# ProjectSchematic.net
KiCad netlist of a schematic drawn in EAGLE
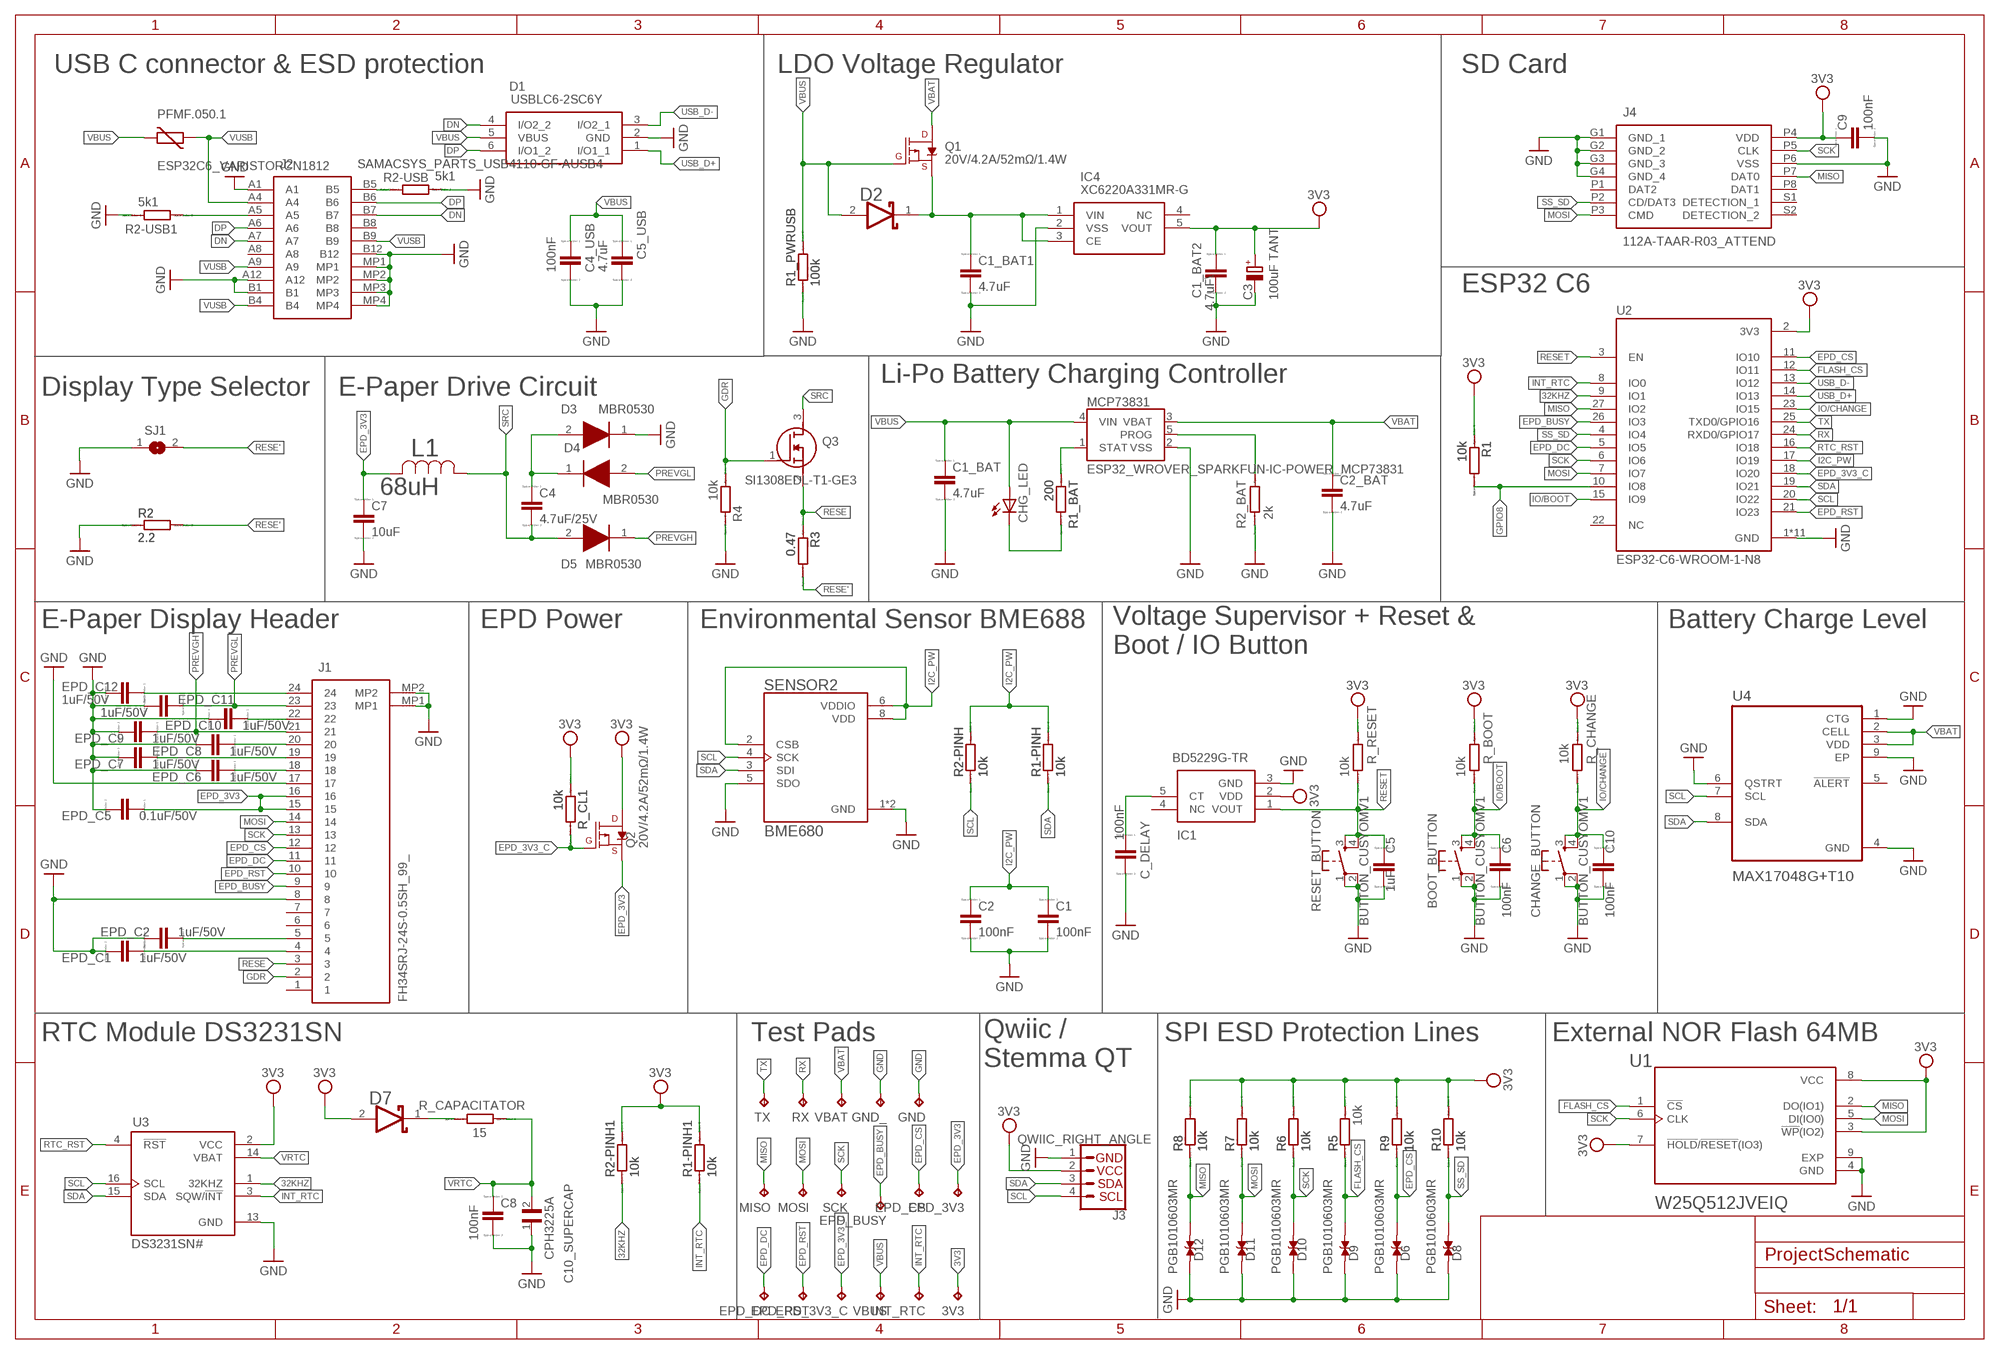
[diagram p0: schematic, sheet 1]

(export (version "E")
  (design (tool "Eeschema 10.0.6"))
  (components
    (comp (ref "3V3")
      (value "TPTP20R")
      (footprint "eagle-import:TP20R")
      (libsource (lib "eagle-import") (part "TPTP20R"))
    )
    (comp (ref "BOOT_BUTTON")
      (value "BUTTON_CUSYOMV1")
      (footprint "eagle-import:MYBUTTON")
      (libsource (lib "eagle-import") (part "BUTTON_CUSYOMV1"))
    )
    (comp (ref "C1")
      (value "100nF")
      (footprint "eagle-import:ESP32_WROVER_EAGLE-LTSPICE_C0402")
      (libsource (lib "eagle-import") (part "ESP32_WROVER_EAGLE-LTSPICE_CC0402"))
    )
    (comp (ref "C1_BAT")
      (value "4.7uF")
      (footprint "eagle-import:ESP32_WROVER_EAGLE-LTSPICE_C0402")
      (libsource (lib "eagle-import") (part "ESP32_WROVER_EAGLE-LTSPICE_CC0402"))
    )
    (comp (ref "C1_BAT1")
      (value "4.7uF")
      (footprint "eagle-import:ESP32_WROVER_EAGLE-LTSPICE_C0402")
      (libsource (lib "eagle-import") (part "ESP32_WROVER_EAGLE-LTSPICE_CC0402"))
    )
    (comp (ref "C1_BAT2")
      (value "4.7uF\\")
      (footprint "eagle-import:ESP32_WROVER_EAGLE-LTSPICE_C0402")
      (libsource (lib "eagle-import") (part "ESP32_WROVER_EAGLE-LTSPICE_CC0402"))
    )
    (comp (ref "C2")
      (value "100nF")
      (footprint "eagle-import:ESP32_WROVER_EAGLE-LTSPICE_C0402")
      (libsource (lib "eagle-import") (part "ESP32_WROVER_EAGLE-LTSPICE_CC0402"))
    )
    (comp (ref "C2_BAT")
      (value "4.7uF")
      (footprint "eagle-import:ESP32_WROVER_EAGLE-LTSPICE_C0402")
      (libsource (lib "eagle-import") (part "ESP32_WROVER_EAGLE-LTSPICE_CC0402"))
    )
    (comp (ref "C3")
      (value "100uF TANT")
      (footprint "eagle-import:RCL_CT3528")
      (libsource (lib "eagle-import") (part "RCL_CPOL-EUCT3528"))
    )
    (comp (ref "C4")
      (value "4.7uF/25V")
      (footprint "eagle-import:ESP32_WROVER_EAGLE-LTSPICE_C0402")
      (libsource (lib "eagle-import") (part "ESP32_WROVER_EAGLE-LTSPICE_CC0402"))
    )
    (comp (ref "C4_USB")
      (value "100nF")
      (footprint "eagle-import:ESP32_WROVER_EAGLE-LTSPICE_C0402")
      (libsource (lib "eagle-import") (part "ESP32_WROVER_EAGLE-LTSPICE_CC0402"))
    )
    (comp (ref "C5")
      (value "1uF")
      (footprint "eagle-import:ESP32_WROVER_EAGLE-LTSPICE_C0402")
      (libsource (lib "eagle-import") (part "ESP32_WROVER_EAGLE-LTSPICE_CC0402"))
    )
    (comp (ref "C5_USB")
      (value "4.7uF")
      (footprint "eagle-import:ESP32_WROVER_EAGLE-LTSPICE_C0402")
      (libsource (lib "eagle-import") (part "ESP32_WROVER_EAGLE-LTSPICE_CC0402"))
    )
    (comp (ref "C6")
      (value "100nF")
      (footprint "eagle-import:ESP32_WROVER_EAGLE-LTSPICE_C0402")
      (libsource (lib "eagle-import") (part "ESP32_WROVER_EAGLE-LTSPICE_CC0402"))
    )
    (comp (ref "C7")
      (value "10uF")
      (footprint "eagle-import:ESP32_WROVER_EAGLE-LTSPICE_C0402")
      (libsource (lib "eagle-import") (part "ESP32_WROVER_EAGLE-LTSPICE_CC0402"))
    )
    (comp (ref "C8")
      (value "100nF")
      (footprint "eagle-import:ESP32_WROVER_EAGLE-LTSPICE_C0402")
      (libsource (lib "eagle-import") (part "ESP32_WROVER_EAGLE-LTSPICE_CC0402"))
    )
    (comp (ref "C9")
      (value "100nF")
      (footprint "eagle-import:ESP32_WROVER_EAGLE-LTSPICE_C0402")
      (libsource (lib "eagle-import") (part "ESP32_WROVER_EAGLE-LTSPICE_CC0402"))
    )
    (comp (ref "C10")
      (value "100nF")
      (footprint "eagle-import:ESP32_WROVER_EAGLE-LTSPICE_C0402")
      (libsource (lib "eagle-import") (part "ESP32_WROVER_EAGLE-LTSPICE_CC0402"))
    )
    (comp (ref "C10_SUPERCAP")
      (value "CPH3225A")
      (footprint "eagle-import:CAPCP3225X100N")
      (fields (field (name "MF") "Seiko Instruments"))
      (libsource (lib "eagle-import") (part "CPH3225A"))
    )
    (comp (ref "CHANGE_BUTTON")
      (value "BUTTON_CUSYOMV1")
      (footprint "eagle-import:MYBUTTON")
      (libsource (lib "eagle-import") (part "BUTTON_CUSYOMV1"))
    )
    (comp (ref "CHG_LED")
      (value "ADAFRUIT_LEDCHIP-LED0603")
      (footprint "eagle-import:ADAFRUIT_CHIP-LED0603")
      (libsource (lib "eagle-import") (part "ADAFRUIT_LEDCHIP-LED0603"))
    )
    (comp (ref "C_DELAY")
      (value "100nF")
      (footprint "eagle-import:ESP32_WROVER_EAGLE-LTSPICE_C0402")
      (libsource (lib "eagle-import") (part "ESP32_WROVER_EAGLE-LTSPICE_CC0402"))
    )
    (comp (ref "D1")
      (value "USBLC6-2SC6Y")
      (footprint "eagle-import:SOT95P280X145-6N")
      (fields (field (name "MF") "STMicroelectronics"))
      (libsource (lib "eagle-import") (part "USBLC6-2SC6Y"))
    )
    (comp (ref "D2")
      (value "ESP32_WROVER_AVX---SD0805S020S1R0_AVX_SD0805S020S1R0_0_0AVX_SD0805S020S1R0_0_0")
      (footprint "eagle-import:ESP32_WROVER_AVX---SD0805S020S1R0_AVX_SD0805S020S1R0_0")
      (fields
        (field (name "DIGIKEY_PART_NUMBER") "478-7800-1-ND")
        (field (name "MF") "AVX")
        (field (name "MOUSER_PART_NUMBER") "581-SD0805S020S1R0")
      )
      (libsource (lib "eagle-import") (part "ESP32_WROVER_AVX---SD0805S020S1R0_AVX_SD0805S020S1R0_0_0AVX_SD0805S020S1R0_0_0"))
    )
    (comp (ref "D3")
      (value "MBR0530")
      (footprint "eagle-import:SOD3716X135N")
      (fields (field (name "MF") "ON Semiconductor"))
      (libsource (lib "eagle-import") (part "MBR0530"))
    )
    (comp (ref "D4")
      (value "MBR0530")
      (footprint "eagle-import:SOD3716X135N")
      (fields (field (name "MF") "ON Semiconductor"))
      (libsource (lib "eagle-import") (part "MBR0530"))
    )
    (comp (ref "D5")
      (value "MBR0530")
      (footprint "eagle-import:SOD3716X135N")
      (fields (field (name "MF") "ON Semiconductor"))
      (libsource (lib "eagle-import") (part "MBR0530"))
    )
    (comp (ref "D6")
      (value "PGB1010603MR")
      (footprint "eagle-import:DIOC1608X36N")
      (fields (field (name "MF") "Littelfuse Inc."))
      (libsource (lib "eagle-import") (part "PGB1010603MR"))
    )
    (comp (ref "D7")
      (value "ESP32_WROVER_AVX---SD0805S020S1R0_AVX_SD0805S020S1R0_0_0AVX_SD0805S020S1R0_0_0")
      (footprint "eagle-import:ESP32_WROVER_AVX---SD0805S020S1R0_AVX_SD0805S020S1R0_0")
      (fields
        (field (name "DIGIKEY_PART_NUMBER") "478-7800-1-ND")
        (field (name "MF") "AVX")
        (field (name "MOUSER_PART_NUMBER") "581-SD0805S020S1R0")
      )
      (libsource (lib "eagle-import") (part "ESP32_WROVER_AVX---SD0805S020S1R0_AVX_SD0805S020S1R0_0_0AVX_SD0805S020S1R0_0_0"))
    )
    (comp (ref "D8")
      (value "PGB1010603MR")
      (footprint "eagle-import:DIOC1608X36N")
      (fields (field (name "MF") "Littelfuse Inc."))
      (libsource (lib "eagle-import") (part "PGB1010603MR"))
    )
    (comp (ref "D9")
      (value "PGB1010603MR")
      (footprint "eagle-import:DIOC1608X36N")
      (fields (field (name "MF") "Littelfuse Inc."))
      (libsource (lib "eagle-import") (part "PGB1010603MR"))
    )
    (comp (ref "D10")
      (value "PGB1010603MR")
      (footprint "eagle-import:DIOC1608X36N")
      (fields (field (name "MF") "Littelfuse Inc."))
      (libsource (lib "eagle-import") (part "PGB1010603MR"))
    )
    (comp (ref "D11")
      (value "PGB1010603MR")
      (footprint "eagle-import:DIOC1608X36N")
      (fields (field (name "MF") "Littelfuse Inc."))
      (libsource (lib "eagle-import") (part "PGB1010603MR"))
    )
    (comp (ref "D12")
      (value "PGB1010603MR")
      (footprint "eagle-import:DIOC1608X36N")
      (fields (field (name "MF") "Littelfuse Inc."))
      (libsource (lib "eagle-import") (part "PGB1010603MR"))
    )
    (comp (ref "EPD_3V3")
      (value "TPTP20R")
      (footprint "eagle-import:TP20R")
      (libsource (lib "eagle-import") (part "TPTP20R"))
    )
    (comp (ref "EPD_3V3_C")
      (value "TPTP20R")
      (footprint "eagle-import:TP20R")
      (libsource (lib "eagle-import") (part "TPTP20R"))
    )
    (comp (ref "EPD_BUSY")
      (value "TPTP20R")
      (footprint "eagle-import:TP20R")
      (libsource (lib "eagle-import") (part "TPTP20R"))
    )
    (comp (ref "EPD_C1")
      (value "1uF/50V")
      (footprint "eagle-import:ESP32_WROVER_EAGLE-LTSPICE_C0402")
      (libsource (lib "eagle-import") (part "ESP32_WROVER_EAGLE-LTSPICE_CC0402"))
    )
    (comp (ref "EPD_C2")
      (value "1uF/50V")
      (footprint "eagle-import:ESP32_WROVER_EAGLE-LTSPICE_C0402")
      (libsource (lib "eagle-import") (part "ESP32_WROVER_EAGLE-LTSPICE_CC0402"))
    )
    (comp (ref "EPD_C5")
      (value "0.1uF/50V")
      (footprint "eagle-import:ESP32_WROVER_EAGLE-LTSPICE_C0402")
      (libsource (lib "eagle-import") (part "ESP32_WROVER_EAGLE-LTSPICE_CC0402"))
    )
    (comp (ref "EPD_C6")
      (value "1uF/50V")
      (footprint "eagle-import:ESP32_WROVER_EAGLE-LTSPICE_C0402")
      (libsource (lib "eagle-import") (part "ESP32_WROVER_EAGLE-LTSPICE_CC0402"))
    )
    (comp (ref "EPD_C7")
      (value "1uF/50V")
      (footprint "eagle-import:ESP32_WROVER_EAGLE-LTSPICE_C0402")
      (libsource (lib "eagle-import") (part "ESP32_WROVER_EAGLE-LTSPICE_CC0402"))
    )
    (comp (ref "EPD_C8")
      (value "1uF/50V")
      (footprint "eagle-import:ESP32_WROVER_EAGLE-LTSPICE_C0402")
      (libsource (lib "eagle-import") (part "ESP32_WROVER_EAGLE-LTSPICE_CC0402"))
    )
    (comp (ref "EPD_C9")
      (value "1uF/50V")
      (footprint "eagle-import:ESP32_WROVER_EAGLE-LTSPICE_C0402")
      (libsource (lib "eagle-import") (part "ESP32_WROVER_EAGLE-LTSPICE_CC0402"))
    )
    (comp (ref "EPD_C10")
      (value "1uF/50V")
      (footprint "eagle-import:ESP32_WROVER_EAGLE-LTSPICE_C0402")
      (libsource (lib "eagle-import") (part "ESP32_WROVER_EAGLE-LTSPICE_CC0402"))
    )
    (comp (ref "EPD_C11")
      (value "1uF/50V")
      (footprint "eagle-import:ESP32_WROVER_EAGLE-LTSPICE_C0402")
      (libsource (lib "eagle-import") (part "ESP32_WROVER_EAGLE-LTSPICE_CC0402"))
    )
    (comp (ref "EPD_C12")
      (value "1uF/50V")
      (footprint "eagle-import:ESP32_WROVER_EAGLE-LTSPICE_C0402")
      (libsource (lib "eagle-import") (part "ESP32_WROVER_EAGLE-LTSPICE_CC0402"))
    )
    (comp (ref "EPD_CS")
      (value "TPTP20R")
      (footprint "eagle-import:TP20R")
      (libsource (lib "eagle-import") (part "TPTP20R"))
    )
    (comp (ref "EPD_DC")
      (value "TPTP20R")
      (footprint "eagle-import:TP20R")
      (libsource (lib "eagle-import") (part "TPTP20R"))
    )
    (comp (ref "EPD_RST")
      (value "TPTP20R")
      (footprint "eagle-import:TP20R")
      (libsource (lib "eagle-import") (part "TPTP20R"))
    )
    (comp (ref "GND")
      (value "TPTP20R")
      (footprint "eagle-import:TP20R")
      (libsource (lib "eagle-import") (part "TPTP20R"))
    )
    (comp (ref "GND_")
      (value "TPTP20R")
      (footprint "eagle-import:TP20R")
      (libsource (lib "eagle-import") (part "TPTP20R"))
    )
    (comp (ref "IC1")
      (value "BD5229G-TR")
      (footprint "eagle-import:SOT95P280X125-5N")
      (fields (field (name "MOUSER_PART_NUMBER") "755-BD5229G-TR"))
      (libsource (lib "eagle-import") (part "BD5229G-TR"))
    )
    (comp (ref "IC4")
      (value "XC6220A331MR-G")
      (footprint "eagle-import:SOT95P280X120-5N")
      (fields (field (name "MOUSER_PART_NUMBER") "865-XC6220A331MR-G"))
      (libsource (lib "eagle-import") (part "XC6220A331MR-G"))
    )
    (comp (ref "INT_RTC")
      (value "TPTP20R")
      (footprint "eagle-import:TP20R")
      (libsource (lib "eagle-import") (part "TPTP20R"))
    )
    (comp (ref "J1")
      (value "FH34SRJ-24S-0.5SH_99_")
      (footprint "eagle-import:FH34SRJ24S05SH99")
      (fields
        (field (name "MANUFACTURER_PART_NUMBER") "FH34SRJ-24S-0.5SH(99)")
        (field (name "MOUSER_PART_NUMBER") "798-FH34SRJ24S05SH99")
      )
      (libsource (lib "eagle-import") (part "FH34SRJ-24S-0.5SH_99_"))
    )
    (comp (ref "J2")
      (value "SAMACSYS_PARTS_USB4110-GF-AUSB4")
      (footprint "eagle-import:SAMACSYS_PARTS_USB4110GFA")
      (libsource (lib "eagle-import") (part "SAMACSYS_PARTS_USB4110-GF-AUSB4"))
    )
    (comp (ref "J3")
      (value "QWIIC_RIGHT_ANGLE")
      (footprint "eagle-import:JST04_1MM_RA")
      (libsource (lib "eagle-import") (part "QWIIC_CONNECTORJS-1MM"))
    )
    (comp (ref "J4")
      (value "112A-TAAR-R03_ATTEND")
      (footprint "eagle-import:112ATAARR03ATTEND")
      (fields (field (name "MANUFACTURER_PART_NUMBER") "112A-TAAR-R03 ATTEND"))
      (libsource (lib "eagle-import") (part "112A-TAAR-R03_ATTEND"))
    )
    (comp (ref "L1")
      (value "68uH")
      (footprint "eagle-import:IND_4828-WE-TPC_WRE")
      (fields
        (field (name "MANUFACTURER_PART_NUMBER") "744043680")
        (field (name "COPYRIGHT") "Copyright (C) 2024 Ultra Librarian. All rights reserved.")
      )
      (libsource (lib "eagle-import") (part "744043680IND_4828-WE-TPC_WRE"))
    )
    (comp (ref "MCP73831")
      (value "ESP32_WROVER_SPARKFUN-IC-POWER_MCP73831")
      (footprint "eagle-import:ESP32_WROVER_SPARKFUN-IC-POWER_SOT23-5")
      (libsource (lib "eagle-import") (part "ESP32_WROVER_SPARKFUN-IC-POWER_MCP73831"))
    )
    (comp (ref "MISO")
      (value "TPTP20R")
      (footprint "eagle-import:TP20R")
      (libsource (lib "eagle-import") (part "TPTP20R"))
    )
    (comp (ref "MOSI")
      (value "TPTP20R")
      (footprint "eagle-import:TP20R")
      (libsource (lib "eagle-import") (part "TPTP20R"))
    )
    (comp (ref "PFMF.050.1")
      (value "ESP32C6_VARISTORCN1812")
      (footprint "eagle-import:ESP32C6_VARISTOR_CT_CN1812")
      (libsource (lib "eagle-import") (part "ESP32C6_VARISTORCN1812"))
    )
    (comp (ref "Q1")
      (value "20V/4.2A/52mΩ/1.4W")
      (footprint "eagle-import:ESP32_WROVER_SPARKFUN-DISCRETESEMI_SOT23-3")
      (libsource (lib "eagle-import") (part "ESP32_WROVER_SPARKFUN-DISCRETESEMI_MOSFET_PCH-DMG2305UX-7"))
    )
    (comp (ref "Q2")
      (value "20V/4.2A/52mΩ/1.4W")
      (footprint "eagle-import:ESP32_WROVER_SPARKFUN-DISCRETESEMI_SOT23-3")
      (libsource (lib "eagle-import") (part "ESP32_WROVER_SPARKFUN-DISCRETESEMI_MOSFET_PCH-DMG2305UX-7"))
    )
    (comp (ref "Q3")
      (value "SI1308EDL-T1-GE3")
      (footprint "eagle-import:SOT65P210X110-3N")
      (fields (field (name "MF") "Vishay Siliconix"))
      (libsource (lib "eagle-import") (part "SI1308EDL-T1-GE3"))
    )
    (comp (ref "R1")
      (value "10k")
      (footprint "eagle-import:ESP32_WROVER_EAGLE-LTSPICE_R0402")
      (libsource (lib "eagle-import") (part "ESP32_WROVER_EAGLE-LTSPICE_RR0402"))
    )
    (comp (ref "R1-PINH")
      (value "10k")
      (footprint "eagle-import:ESP32_WROVER_EAGLE-LTSPICE_R0402")
      (libsource (lib "eagle-import") (part "ESP32_WROVER_EAGLE-LTSPICE_RR0402"))
    )
    (comp (ref "R1-PINH1")
      (value "10k")
      (footprint "eagle-import:ESP32_WROVER_EAGLE-LTSPICE_R0402")
      (libsource (lib "eagle-import") (part "ESP32_WROVER_EAGLE-LTSPICE_RR0402"))
    )
    (comp (ref "R1_BAT")
      (value "200")
      (footprint "eagle-import:ESP32_WROVER_EAGLE-LTSPICE_R0402")
      (libsource (lib "eagle-import") (part "ESP32_WROVER_EAGLE-LTSPICE_RR0402"))
    )
    (comp (ref "R1_PWRUSB")
      (value "100k")
      (footprint "eagle-import:ESP32_WROVER_EAGLE-LTSPICE_R0402")
      (libsource (lib "eagle-import") (part "ESP32_WROVER_EAGLE-LTSPICE_RR0402"))
    )
    (comp (ref "R2")
      (value "2.2")
      (footprint "eagle-import:ESP32_WROVER_EAGLE-LTSPICE_R0402")
      (libsource (lib "eagle-import") (part "ESP32_WROVER_EAGLE-LTSPICE_RR0402"))
    )
    (comp (ref "R2-PINH")
      (value "10k")
      (footprint "eagle-import:ESP32_WROVER_EAGLE-LTSPICE_R0402")
      (libsource (lib "eagle-import") (part "ESP32_WROVER_EAGLE-LTSPICE_RR0402"))
    )
    (comp (ref "R2-PINH1")
      (value "10k")
      (footprint "eagle-import:ESP32_WROVER_EAGLE-LTSPICE_R0402")
      (libsource (lib "eagle-import") (part "ESP32_WROVER_EAGLE-LTSPICE_RR0402"))
    )
    (comp (ref "R2-USB")
      (value "5k1")
      (footprint "eagle-import:ESP32_WROVER_EAGLE-LTSPICE_R0402")
      (libsource (lib "eagle-import") (part "ESP32_WROVER_EAGLE-LTSPICE_RR0402"))
    )
    (comp (ref "R2-USB1")
      (value "5k1")
      (footprint "eagle-import:ESP32_WROVER_EAGLE-LTSPICE_R0402")
      (libsource (lib "eagle-import") (part "ESP32_WROVER_EAGLE-LTSPICE_RR0402"))
    )
    (comp (ref "R2_BAT")
      (value "2k")
      (footprint "eagle-import:ESP32_WROVER_EAGLE-LTSPICE_R0402")
      (libsource (lib "eagle-import") (part "ESP32_WROVER_EAGLE-LTSPICE_RR0402"))
    )
    (comp (ref "R3")
      (value "0.47")
      (footprint "eagle-import:ESP32_WROVER_EAGLE-LTSPICE_R0402")
      (libsource (lib "eagle-import") (part "ESP32_WROVER_EAGLE-LTSPICE_RR0402"))
    )
    (comp (ref "R4")
      (value "10k")
      (footprint "eagle-import:ESP32_WROVER_EAGLE-LTSPICE_R0402")
      (libsource (lib "eagle-import") (part "ESP32_WROVER_EAGLE-LTSPICE_RR0402"))
    )
    (comp (ref "R5")
      (value "10k")
      (footprint "eagle-import:ESP32_WROVER_EAGLE-LTSPICE_R0402")
      (libsource (lib "eagle-import") (part "ESP32_WROVER_EAGLE-LTSPICE_RR0402"))
    )
    (comp (ref "R6")
      (value "10k")
      (footprint "eagle-import:ESP32_WROVER_EAGLE-LTSPICE_R0402")
      (libsource (lib "eagle-import") (part "ESP32_WROVER_EAGLE-LTSPICE_RR0402"))
    )
    (comp (ref "R7")
      (value "10k")
      (footprint "eagle-import:ESP32_WROVER_EAGLE-LTSPICE_R0402")
      (libsource (lib "eagle-import") (part "ESP32_WROVER_EAGLE-LTSPICE_RR0402"))
    )
    (comp (ref "R8")
      (value "10k")
      (footprint "eagle-import:ESP32_WROVER_EAGLE-LTSPICE_R0402")
      (libsource (lib "eagle-import") (part "ESP32_WROVER_EAGLE-LTSPICE_RR0402"))
    )
    (comp (ref "R9")
      (value "10k")
      (footprint "eagle-import:ESP32_WROVER_EAGLE-LTSPICE_R0402")
      (libsource (lib "eagle-import") (part "ESP32_WROVER_EAGLE-LTSPICE_RR0402"))
    )
    (comp (ref "R10")
      (value "10k")
      (footprint "eagle-import:ESP32_WROVER_EAGLE-LTSPICE_R0402")
      (libsource (lib "eagle-import") (part "ESP32_WROVER_EAGLE-LTSPICE_RR0402"))
    )
    (comp (ref "RESET_BUTTON")
      (value "BUTTON_CUSYOMV1")
      (footprint "eagle-import:MYBUTTON")
      (libsource (lib "eagle-import") (part "BUTTON_CUSYOMV1"))
    )
    (comp (ref "RX")
      (value "TPTP20R")
      (footprint "eagle-import:TP20R")
      (libsource (lib "eagle-import") (part "TPTP20R"))
    )
    (comp (ref "R_BOOT")
      (value "10k")
      (footprint "eagle-import:ESP32_WROVER_EAGLE-LTSPICE_R0402")
      (libsource (lib "eagle-import") (part "ESP32_WROVER_EAGLE-LTSPICE_RR0402"))
    )
    (comp (ref "R_CAPACITATOR")
      (value "15")
      (footprint "eagle-import:ESP32_WROVER_EAGLE-LTSPICE_R0402")
      (libsource (lib "eagle-import") (part "ESP32_WROVER_EAGLE-LTSPICE_RR0402"))
    )
    (comp (ref "R_CHANGE")
      (value "10k")
      (footprint "eagle-import:ESP32_WROVER_EAGLE-LTSPICE_R0402")
      (libsource (lib "eagle-import") (part "ESP32_WROVER_EAGLE-LTSPICE_RR0402"))
    )
    (comp (ref "R_CL1")
      (value "10k")
      (footprint "eagle-import:ESP32_WROVER_EAGLE-LTSPICE_R0402")
      (libsource (lib "eagle-import") (part "ESP32_WROVER_EAGLE-LTSPICE_RR0402"))
    )
    (comp (ref "R_RESET")
      (value "10k")
      (footprint "eagle-import:ESP32_WROVER_EAGLE-LTSPICE_R0402")
      (libsource (lib "eagle-import") (part "ESP32_WROVER_EAGLE-LTSPICE_RR0402"))
    )
    (comp (ref "SCK")
      (value "TPTP20R")
      (footprint "eagle-import:TP20R")
      (libsource (lib "eagle-import") (part "TPTP20R"))
    )
    (comp (ref "SENSOR2")
      (value "BME680")
      (footprint "eagle-import:ESP32_WROVER_BME680_PSON80P300X300X100-8N")
      (fields (field (name "MF") "Bosch Sensortec"))
      (libsource (lib "eagle-import") (part "ESP32_WROVER_BME680_BME680"))
    )
    (comp (ref "SJ1") (value "SJ") (footprint "eagle-import:SJ") (libsource (lib "eagle-import") (part "SJ")))
    (comp (ref "TX")
      (value "TPTP20R")
      (footprint "eagle-import:TP20R")
      (libsource (lib "eagle-import") (part "TPTP20R"))
    )
    (comp (ref "U1")
      (value "W25Q512JVEIQ")
      (footprint "eagle-import:SON127P600X800X80-9N")
      (fields (field (name "MF") "Winbond Electronics"))
      (libsource (lib "eagle-import") (part "W25Q512JVEIQ"))
    )
    (comp (ref "U2")
      (value "ESP32-C6-WROOM-1-N8")
      (footprint "eagle-import:XCVR_ESP32-C6-WROOM-1-N8")
      (fields (field (name "MF") "Espressif Systems"))
      (libsource (lib "eagle-import") (part "ESP32-C6-WROOM-1-N8"))
    )
    (comp (ref "U3")
      (value "DS3231SN#")
      (footprint "eagle-import:SOIC127P1032X265-16N")
      (fields (field (name "MF") "Analog Devices"))
      (libsource (lib "eagle-import") (part "DS3231SN#"))
    )
    (comp (ref "U4")
      (value "MAX17048G+T10")
      (footprint "eagle-import:SON50P200X200X80-9N")
      (fields (field (name "MF") "Analog Devices"))
      (libsource (lib "eagle-import") (part "MAX17048G+T10"))
    )
    (comp (ref "VBAT")
      (value "TPTP20R")
      (footprint "eagle-import:TP20R")
      (libsource (lib "eagle-import") (part "TPTP20R"))
    )
    (comp (ref "VBUS")
      (value "TPTP20R")
      (footprint "eagle-import:TP20R")
      (libsource (lib "eagle-import") (part "TPTP20R"))
    )
  )
  (nets
    (net (code "1") (name "3V3") (class "Default")
      (node (ref "3V3") (pin "TP") (pinfunction "TP_TP") (pintype "input"))
      (node (ref "C1_BAT2") (pin "1") (pinfunction "1_1") (pintype "passive"))
      (node (ref "C3") (pin "+") (pinfunction "+_+") (pintype "passive"))
      (node (ref "C9") (pin "1") (pinfunction "1_1") (pintype "passive"))
      (node (ref "D7") (pin "2") (pinfunction "ANODE_2") (pintype "bidirectional"))
      (node (ref "IC1") (pin "2") (pinfunction "VDD_2") (pintype "bidirectional"))
      (node (ref "IC4") (pin "5") (pinfunction "VOUT_5") (pintype "bidirectional"))
      (node (ref "J3") (pin "2") (pinfunction "2_2") (pintype "power_in"))
      (node (ref "J4") (pin "P4") (pinfunction "VDD_P4") (pintype "bidirectional"))
      (node (ref "Q2") (pin "3") (pinfunction "D_3") (pintype "bidirectional"))
      (node (ref "R1") (pin "1") (pinfunction "1_1") (pintype "passive"))
      (node (ref "R1-PINH1") (pin "2") (pinfunction "2_2") (pintype "passive"))
      (node (ref "R10") (pin "2") (pinfunction "2_2") (pintype "passive"))
      (node (ref "R2-PINH1") (pin "2") (pinfunction "2_2") (pintype "passive"))
      (node (ref "R5") (pin "2") (pinfunction "2_2") (pintype "passive"))
      (node (ref "R6") (pin "2") (pinfunction "2_2") (pintype "passive"))
      (node (ref "R7") (pin "2") (pinfunction "2_2") (pintype "passive"))
      (node (ref "R8") (pin "2") (pinfunction "2_2") (pintype "passive"))
      (node (ref "R9") (pin "2") (pinfunction "2_2") (pintype "passive"))
      (node (ref "R_BOOT") (pin "2") (pinfunction "2_2") (pintype "passive"))
      (node (ref "R_CHANGE") (pin "2") (pinfunction "2_2") (pintype "passive"))
      (node (ref "R_CL1") (pin "1") (pinfunction "1_1") (pintype "passive"))
      (node (ref "R_RESET") (pin "2") (pinfunction "2_2") (pintype "passive"))
      (node (ref "U1") (pin "3") (pinfunction "~{WP}(IO2)_3") (pintype "bidirectional"))
      (node (ref "U1") (pin "7") (pinfunction "~{HOLD}/~{RESET}(IO3)_7") (pintype "bidirectional"))
      (node (ref "U1") (pin "8") (pinfunction "VCC_8") (pintype "power_in"))
      (node (ref "U2") (pin "2") (pinfunction "3V3_2") (pintype "power_in"))
      (node (ref "U3") (pin "2") (pinfunction "VCC_2") (pintype "power_in"))
    )
    (net (code "2") (name "32KHZ") (class "Default")
      (node (ref "R2-PINH1") (pin "1") (pinfunction "1_1") (pintype "passive"))
      (node (ref "U2") (pin "9") (pinfunction "IO1_9") (pintype "bidirectional"))
      (node (ref "U3") (pin "1") (pinfunction "32KHZ_1") (pintype "output"))
    )
    (net (code "3") (name "DN") (class "Default")
      (node (ref "D1") (pin "4") (pinfunction "I/O2_2_4") (pintype "bidirectional"))
      (node (ref "J2") (pin "A7") (pinfunction "A7_A7") (pintype "bidirectional"))
      (node (ref "J2") (pin "B7") (pinfunction "B7_B7") (pintype "bidirectional"))
    )
    (net (code "4") (name "DP") (class "Default")
      (node (ref "D1") (pin "6") (pinfunction "I/O1_2_6") (pintype "bidirectional"))
      (node (ref "J2") (pin "A6") (pinfunction "A6_A6") (pintype "bidirectional"))
      (node (ref "J2") (pin "B6") (pinfunction "B6_B6") (pintype "bidirectional"))
    )
    (net (code "5") (name "EPD_3V3") (class "Default")
      (node (ref "C7") (pin "1") (pinfunction "1_1") (pintype "passive"))
      (node (ref "EPD_3V3") (pin "TP") (pinfunction "TP_TP") (pintype "input"))
      (node (ref "EPD_C5") (pin "1") (pinfunction "1_1") (pintype "passive"))
      (node (ref "J1") (pin "15") (pinfunction "15_15") (pintype "bidirectional"))
      (node (ref "J1") (pin "16") (pinfunction "16_16") (pintype "bidirectional"))
      (node (ref "L1") (pin "2") (pinfunction "2_2") (pintype "passive"))
      (node (ref "Q2") (pin "2") (pinfunction "S_2") (pintype "bidirectional"))
    )
    (net (code "6") (name "EPD_3V3_C") (class "Default")
      (node (ref "EPD_3V3_C") (pin "TP") (pinfunction "TP_TP") (pintype "input"))
      (node (ref "Q2") (pin "1") (pinfunction "G_1") (pintype "bidirectional"))
      (node (ref "R_CL1") (pin "2") (pinfunction "2_2") (pintype "passive"))
      (node (ref "U2") (pin "18") (pinfunction "IO20_18") (pintype "bidirectional"))
    )
    (net (code "7") (name "EPD_BUSY") (class "Default")
      (node (ref "EPD_BUSY") (pin "TP") (pinfunction "TP_TP") (pintype "input"))
      (node (ref "J1") (pin "9") (pinfunction "9_9") (pintype "bidirectional"))
      (node (ref "U2") (pin "26") (pinfunction "IO3_26") (pintype "bidirectional"))
    )
    (net (code "8") (name "EPD_CS") (class "Default")
      (node (ref "D6") (pin "2") (pinfunction "2_2") (pintype "passive"))
      (node (ref "EPD_CS") (pin "TP") (pinfunction "TP_TP") (pintype "input"))
      (node (ref "J1") (pin "12") (pinfunction "12_12") (pintype "bidirectional"))
      (node (ref "R9") (pin "1") (pinfunction "1_1") (pintype "passive"))
      (node (ref "U2") (pin "11") (pinfunction "IO10_11") (pintype "bidirectional"))
    )
    (net (code "9") (name "EPD_DC") (class "Default")
      (node (ref "EPD_DC") (pin "TP") (pinfunction "TP_TP") (pintype "input"))
      (node (ref "J1") (pin "11") (pinfunction "11_11") (pintype "bidirectional"))
      (node (ref "U2") (pin "5") (pinfunction "IO5_5") (pintype "bidirectional"))
    )
    (net (code "10") (name "EPD_RST") (class "Default")
      (node (ref "EPD_RST") (pin "TP") (pinfunction "TP_TP") (pintype "input"))
      (node (ref "J1") (pin "10") (pinfunction "10_10") (pintype "bidirectional"))
      (node (ref "U2") (pin "21") (pinfunction "IO23_21") (pintype "bidirectional"))
    )
    (net (code "11") (name "FLASH_CS") (class "Default")
      (node (ref "D9") (pin "2") (pinfunction "2_2") (pintype "passive"))
      (node (ref "R5") (pin "1") (pinfunction "1_1") (pintype "passive"))
      (node (ref "U1") (pin "1") (pinfunction "~{CS}_1") (pintype "input"))
      (node (ref "U2") (pin "12") (pinfunction "IO11_12") (pintype "bidirectional"))
    )
    (net (code "12") (name "GDR") (class "Default")
      (node (ref "J1") (pin "2") (pinfunction "2_2") (pintype "bidirectional"))
      (node (ref "Q3") (pin "1") (pinfunction "G_1") (pintype "bidirectional"))
      (node (ref "R4") (pin "1") (pinfunction "1_1") (pintype "passive"))
    )
    (net (code "13") (name "GND") (class "Default")
      (node (ref "BOOT_BUTTON") (pin "1") (pinfunction "1_1") (pintype "passive"))
      (node (ref "BOOT_BUTTON") (pin "2") (pinfunction "2_2") (pintype "passive"))
      (node (ref "C1") (pin "2") (pinfunction "2_2") (pintype "passive"))
      (node (ref "C10") (pin "2") (pinfunction "2_2") (pintype "passive"))
      (node (ref "C10_SUPERCAP") (pin "1") (pinfunction "1_1") (pintype "passive"))
      (node (ref "C1_BAT") (pin "2") (pinfunction "2_2") (pintype "passive"))
      (node (ref "C1_BAT1") (pin "2") (pinfunction "2_2") (pintype "passive"))
      (node (ref "C1_BAT2") (pin "2") (pinfunction "2_2") (pintype "passive"))
      (node (ref "C2") (pin "2") (pinfunction "2_2") (pintype "passive"))
      (node (ref "C2_BAT") (pin "2") (pinfunction "2_2") (pintype "passive"))
      (node (ref "C3") (pin "-") (pinfunction "-_-") (pintype "passive"))
      (node (ref "C4_USB") (pin "2") (pinfunction "2_2") (pintype "passive"))
      (node (ref "C5") (pin "2") (pinfunction "2_2") (pintype "passive"))
      (node (ref "C5_USB") (pin "2") (pinfunction "2_2") (pintype "passive"))
      (node (ref "C6") (pin "2") (pinfunction "2_2") (pintype "passive"))
      (node (ref "C7") (pin "2") (pinfunction "2_2") (pintype "passive"))
      (node (ref "C8") (pin "2") (pinfunction "2_2") (pintype "passive"))
      (node (ref "C9") (pin "2") (pinfunction "2_2") (pintype "passive"))
      (node (ref "CHANGE_BUTTON") (pin "1") (pinfunction "1_1") (pintype "passive"))
      (node (ref "CHANGE_BUTTON") (pin "2") (pinfunction "2_2") (pintype "passive"))
      (node (ref "C_DELAY") (pin "2") (pinfunction "2_2") (pintype "passive"))
      (node (ref "D1") (pin "2") (pinfunction "GND_2") (pintype "bidirectional"))
      (node (ref "D10") (pin "1") (pinfunction "1_1") (pintype "passive"))
      (node (ref "D11") (pin "1") (pinfunction "1_1") (pintype "passive"))
      (node (ref "D12") (pin "1") (pinfunction "1_1") (pintype "passive"))
      (node (ref "D3") (pin "1") (pinfunction "K_1") (pintype "bidirectional"))
      (node (ref "D6") (pin "1") (pinfunction "1_1") (pintype "passive"))
      (node (ref "D8") (pin "1") (pinfunction "1_1") (pintype "passive"))
      (node (ref "D9") (pin "1") (pinfunction "1_1") (pintype "passive"))
      (node (ref "EPD_C1") (pin "2") (pinfunction "2_2") (pintype "passive"))
      (node (ref "EPD_C10") (pin "2") (pinfunction "2_2") (pintype "passive"))
      (node (ref "EPD_C11") (pin "2") (pinfunction "2_2") (pintype "passive"))
      (node (ref "EPD_C12") (pin "2") (pinfunction "2_2") (pintype "passive"))
      (node (ref "EPD_C2") (pin "2") (pinfunction "2_2") (pintype "passive"))
      (node (ref "EPD_C5") (pin "2") (pinfunction "2_2") (pintype "passive"))
      (node (ref "EPD_C6") (pin "2") (pinfunction "2_2") (pintype "passive"))
      (node (ref "EPD_C7") (pin "2") (pinfunction "2_2") (pintype "passive"))
      (node (ref "EPD_C8") (pin "2") (pinfunction "2_2") (pintype "passive"))
      (node (ref "EPD_C9") (pin "2") (pinfunction "2_2") (pintype "passive"))
      (node (ref "GND") (pin "TP") (pinfunction "TP_TP") (pintype "input"))
      (node (ref "GND_") (pin "TP") (pinfunction "TP_TP") (pintype "input"))
      (node (ref "IC1") (pin "3") (pinfunction "GND_3") (pintype "bidirectional"))
      (node (ref "IC4") (pin "2") (pinfunction "VSS_2") (pintype "bidirectional"))
      (node (ref "J1") (pin "17") (pinfunction "17_17") (pintype "bidirectional"))
      (node (ref "J1") (pin "8") (pinfunction "8_8") (pintype "bidirectional"))
      (node (ref "J1") (pin "MP1") (pinfunction "MP1_MP1") (pintype "bidirectional"))
      (node (ref "J1") (pin "MP2") (pinfunction "MP2_MP2") (pintype "bidirectional"))
      (node (ref "J2") (pin "A1") (pinfunction "A1_A1") (pintype "bidirectional"))
      (node (ref "J2") (pin "A12") (pinfunction "A12_A12") (pintype "bidirectional"))
      (node (ref "J2") (pin "B1") (pinfunction "B1_B1") (pintype "bidirectional"))
      (node (ref "J2") (pin "B12") (pinfunction "B12_B12") (pintype "bidirectional"))
      (node (ref "J2") (pin "MP1") (pinfunction "MP1_MP1") (pintype "bidirectional"))
      (node (ref "J2") (pin "MP2") (pinfunction "MP2_MP2") (pintype "bidirectional"))
      (node (ref "J2") (pin "MP3") (pinfunction "MP3_MP3") (pintype "bidirectional"))
      (node (ref "J2") (pin "MP4") (pinfunction "MP4_MP4") (pintype "bidirectional"))
      (node (ref "J3") (pin "1") (pinfunction "1_1") (pintype "power_in"))
      (node (ref "J4") (pin "G1") (pinfunction "GND_1_G1") (pintype "bidirectional"))
      (node (ref "J4") (pin "G2") (pinfunction "GND_2_G2") (pintype "bidirectional"))
      (node (ref "J4") (pin "G3") (pinfunction "GND_3_G3") (pintype "bidirectional"))
      (node (ref "J4") (pin "G4") (pinfunction "GND_4_G4") (pintype "bidirectional"))
      (node (ref "J4") (pin "P6") (pinfunction "VSS_P6") (pintype "bidirectional"))
      (node (ref "MCP73831") (pin "2") (pinfunction "VSS_2") (pintype "power_in"))
      (node (ref "R1_PWRUSB") (pin "1") (pinfunction "1_1") (pintype "passive"))
      (node (ref "R2") (pin "1") (pinfunction "1_1") (pintype "passive"))
      (node (ref "R2-USB") (pin "2") (pinfunction "2_2") (pintype "passive"))
      (node (ref "R2-USB1") (pin "1") (pinfunction "1_1") (pintype "passive"))
      (node (ref "R2_BAT") (pin "2") (pinfunction "2_2") (pintype "passive"))
      (node (ref "R4") (pin "2") (pinfunction "2_2") (pintype "passive"))
      (node (ref "RESET_BUTTON") (pin "1") (pinfunction "1_1") (pintype "passive"))
      (node (ref "RESET_BUTTON") (pin "2") (pinfunction "2_2") (pintype "passive"))
      (node (ref "SENSOR2") (pin "1") (pinfunction "GND_1") (pintype "power_in"))
      (node (ref "SENSOR2") (pin "5") (pinfunction "SDO_5") (pintype "bidirectional"))
      (node (ref "SENSOR2") (pin "7") (pinfunction "GND_7") (pintype "power_in"))
      (node (ref "SJ1") (pin "1") (pinfunction "1_1") (pintype "passive"))
      (node (ref "U1") (pin "4") (pinfunction "GND_4") (pintype "power_in"))
      (node (ref "U1") (pin "9") (pinfunction "EXP_9") (pintype "passive"))
      (node (ref "U2") (pin "1") (pinfunction "GND_1") (pintype "power_in"))
      (node (ref "U2") (pin "28") (pinfunction "GND_28") (pintype "power_in"))
      (node (ref "U2") (pin "29_1") (pinfunction "GND_29_1") (pintype "power_in"))
      (node (ref "U2") (pin "29_2") (pinfunction "GND_29_2") (pintype "power_in"))
      (node (ref "U2") (pin "29_3") (pinfunction "GND_29_3") (pintype "power_in"))
      (node (ref "U2") (pin "29_4") (pinfunction "GND_29_4") (pintype "power_in"))
      (node (ref "U2") (pin "29_5") (pinfunction "GND_29_5") (pintype "power_in"))
      (node (ref "U2") (pin "29_6") (pinfunction "GND_29_6") (pintype "power_in"))
      (node (ref "U2") (pin "29_7") (pinfunction "GND_29_7") (pintype "power_in"))
      (node (ref "U2") (pin "29_8") (pinfunction "GND_29_8") (pintype "power_in"))
      (node (ref "U2") (pin "29_9") (pinfunction "GND_29_9") (pintype "power_in"))
      (node (ref "U3") (pin "13") (pinfunction "GND_13") (pintype "power_in"))
      (node (ref "U4") (pin "1") (pinfunction "CTG_1") (pintype "power_in"))
      (node (ref "U4") (pin "4") (pinfunction "GND_4") (pintype "power_in"))
      (node (ref "U4") (pin "6") (pinfunction "QSTRT_6") (pintype "input"))
      (node (ref "U4") (pin "9") (pinfunction "EP_9") (pintype "power_in"))
    )
    (net (code "14") (name "GPIO8") (class "Default")
      (node (ref "R1") (pin "2") (pinfunction "2_2") (pintype "passive"))
      (node (ref "U2") (pin "10") (pinfunction "IO8_10") (pintype "bidirectional"))
    )
    (net (code "15") (name "I2C_PW") (class "Default")
      (node (ref "C1") (pin "1") (pinfunction "1_1") (pintype "passive"))
      (node (ref "C2") (pin "1") (pinfunction "1_1") (pintype "passive"))
      (node (ref "R1-PINH") (pin "2") (pinfunction "2_2") (pintype "passive"))
      (node (ref "R2-PINH") (pin "2") (pinfunction "2_2") (pintype "passive"))
      (node (ref "SENSOR2") (pin "2") (pinfunction "CSB_2") (pintype "input"))
      (node (ref "SENSOR2") (pin "6") (pinfunction "VDDIO_6") (pintype "power_in"))
      (node (ref "SENSOR2") (pin "8") (pinfunction "VDD_8") (pintype "power_in"))
      (node (ref "U2") (pin "17") (pinfunction "IO19_17") (pintype "bidirectional"))
    )
    (net (code "16") (name "INT_RTC") (class "Default")
      (node (ref "INT_RTC") (pin "TP") (pinfunction "TP_TP") (pintype "input"))
      (node (ref "R1-PINH1") (pin "1") (pinfunction "1_1") (pintype "passive"))
      (node (ref "U2") (pin "8") (pinfunction "IO0_8") (pintype "bidirectional"))
      (node (ref "U3") (pin "3") (pinfunction "SQW/~{INT}_3") (pintype "output"))
    )
    (net (code "17") (name "IO{slash}BOOT") (class "Default")
      (node (ref "BOOT_BUTTON") (pin "3") (pinfunction "3_3") (pintype "passive"))
      (node (ref "BOOT_BUTTON") (pin "4") (pinfunction "4_4") (pintype "passive"))
      (node (ref "C6") (pin "1") (pinfunction "1_1") (pintype "passive"))
      (node (ref "R_BOOT") (pin "1") (pinfunction "1_1") (pintype "passive"))
      (node (ref "U2") (pin "15") (pinfunction "IO9_15") (pintype "bidirectional"))
    )
    (net (code "18") (name "IO{slash}CHANGE") (class "Default")
      (node (ref "C10") (pin "1") (pinfunction "1_1") (pintype "passive"))
      (node (ref "CHANGE_BUTTON") (pin "3") (pinfunction "3_3") (pintype "passive"))
      (node (ref "CHANGE_BUTTON") (pin "4") (pinfunction "4_4") (pintype "passive"))
      (node (ref "R_CHANGE") (pin "1") (pinfunction "1_1") (pintype "passive"))
      (node (ref "U2") (pin "23") (pinfunction "IO15_23") (pintype "bidirectional"))
    )
    (net (code "19") (name "MISO") (class "Default")
      (node (ref "D12") (pin "2") (pinfunction "2_2") (pintype "passive"))
      (node (ref "J4") (pin "P7") (pinfunction "DAT0_P7") (pintype "bidirectional"))
      (node (ref "MISO") (pin "TP") (pinfunction "TP_TP") (pintype "input"))
      (node (ref "R8") (pin "1") (pinfunction "1_1") (pintype "passive"))
      (node (ref "U1") (pin "2") (pinfunction "DO(IO1)_2") (pintype "bidirectional"))
      (node (ref "U2") (pin "27") (pinfunction "IO2_27") (pintype "bidirectional"))
    )
    (net (code "20") (name "MOSI") (class "Default")
      (node (ref "D11") (pin "2") (pinfunction "2_2") (pintype "passive"))
      (node (ref "J1") (pin "14") (pinfunction "14_14") (pintype "bidirectional"))
      (node (ref "J4") (pin "P3") (pinfunction "CMD_P3") (pintype "bidirectional"))
      (node (ref "MOSI") (pin "TP") (pinfunction "TP_TP") (pintype "input"))
      (node (ref "R7") (pin "1") (pinfunction "1_1") (pintype "passive"))
      (node (ref "U1") (pin "5") (pinfunction "DI(IO0)_5") (pintype "bidirectional"))
      (node (ref "U2") (pin "7") (pinfunction "IO7_7") (pintype "bidirectional"))
    )
    (net (code "21") (name "Net-(CHG_LED-PadC)") (class "Default")
      (node (ref "CHG_LED") (pin "C") (pinfunction "C_C") (pintype "passive"))
      (node (ref "R1_BAT") (pin "2") (pinfunction "2_2") (pintype "passive"))
    )
    (net (code "22") (name "Net-(D2-CATHODE)") (class "Default")
      (node (ref "C1_BAT1") (pin "1") (pinfunction "1_1") (pintype "passive"))
      (node (ref "D2") (pin "1") (pinfunction "CATHODE_1") (pintype "bidirectional"))
      (node (ref "IC4") (pin "1") (pinfunction "VIN_1") (pintype "bidirectional"))
      (node (ref "IC4") (pin "3") (pinfunction "CE_3") (pintype "bidirectional"))
      (node (ref "Q1") (pin "2") (pinfunction "S_2") (pintype "bidirectional"))
    )
    (net (code "23") (name "Net-(D3-A)") (class "Default")
      (node (ref "C4") (pin "1") (pinfunction "1_1") (pintype "passive"))
      (node (ref "D3") (pin "2") (pinfunction "A_2") (pintype "bidirectional"))
      (node (ref "D4") (pin "1") (pinfunction "K_1") (pintype "bidirectional"))
    )
    (net (code "24") (name "Net-(D7-CATHODE)") (class "Default")
      (node (ref "D7") (pin "1") (pinfunction "CATHODE_1") (pintype "bidirectional"))
      (node (ref "R_CAPACITATOR") (pin "2") (pinfunction "2_2") (pintype "passive"))
    )
    (net (code "25") (name "Net-(EPD_C1-Pad1)") (class "Default")
      (node (ref "EPD_C1") (pin "1") (pinfunction "1_1") (pintype "passive"))
      (node (ref "J1") (pin "4") (pinfunction "4_4") (pintype "bidirectional"))
    )
    (net (code "26") (name "Net-(EPD_C2-Pad1)") (class "Default")
      (node (ref "EPD_C2") (pin "1") (pinfunction "1_1") (pintype "passive"))
      (node (ref "J1") (pin "5") (pinfunction "5_5") (pintype "bidirectional"))
    )
    (net (code "27") (name "Net-(EPD_C6-Pad1)") (class "Default")
      (node (ref "EPD_C6") (pin "1") (pinfunction "1_1") (pintype "passive"))
      (node (ref "J1") (pin "18") (pinfunction "18_18") (pintype "bidirectional"))
    )
    (net (code "28") (name "Net-(EPD_C7-Pad1)") (class "Default")
      (node (ref "EPD_C7") (pin "1") (pinfunction "1_1") (pintype "passive"))
      (node (ref "J1") (pin "19") (pinfunction "19_19") (pintype "bidirectional"))
    )
    (net (code "29") (name "Net-(EPD_C8-Pad1)") (class "Default")
      (node (ref "EPD_C8") (pin "1") (pinfunction "1_1") (pintype "passive"))
      (node (ref "J1") (pin "20") (pinfunction "20_20") (pintype "bidirectional"))
    )
    (net (code "30") (name "Net-(EPD_C10-Pad1)") (class "Default")
      (node (ref "EPD_C10") (pin "1") (pinfunction "1_1") (pintype "passive"))
      (node (ref "J1") (pin "22") (pinfunction "22_22") (pintype "bidirectional"))
    )
    (net (code "31") (name "Net-(EPD_C12-Pad1)") (class "Default")
      (node (ref "EPD_C12") (pin "1") (pinfunction "1_1") (pintype "passive"))
      (node (ref "J1") (pin "24") (pinfunction "24_24") (pintype "bidirectional"))
    )
    (net (code "32") (name "Net-(IC1-CT)") (class "Default")
      (node (ref "C_DELAY") (pin "1") (pinfunction "1_1") (pintype "passive"))
      (node (ref "IC1") (pin "5") (pinfunction "CT_5") (pintype "bidirectional"))
    )
    (net (code "33") (name "Net-(J2-PadA5)") (class "Default")
      (node (ref "J2") (pin "A5") (pinfunction "A5_A5") (pintype "bidirectional"))
      (node (ref "R2-USB1") (pin "2") (pinfunction "2_2") (pintype "passive"))
    )
    (net (code "34") (name "Net-(J2-PadB5)") (class "Default")
      (node (ref "J2") (pin "B5") (pinfunction "B5_B5") (pintype "bidirectional"))
      (node (ref "R2-USB") (pin "1") (pinfunction "1_1") (pintype "passive"))
    )
    (net (code "35") (name "Net-(MCP73831-PROG)") (class "Default")
      (node (ref "MCP73831") (pin "5") (pinfunction "PROG_5") (pintype "input"))
      (node (ref "R2_BAT") (pin "1") (pinfunction "1_1") (pintype "passive"))
    )
    (net (code "36") (name "Net-(MCP73831-STAT)") (class "Default")
      (node (ref "MCP73831") (pin "1") (pinfunction "STAT_1") (pintype "output"))
      (node (ref "R1_BAT") (pin "1") (pinfunction "1_1") (pintype "passive"))
    )
    (net (code "37") (name "PREVGH") (class "Default")
      (node (ref "D5") (pin "1") (pinfunction "K_1") (pintype "bidirectional"))
      (node (ref "EPD_C9") (pin "1") (pinfunction "1_1") (pintype "passive"))
      (node (ref "J1") (pin "21") (pinfunction "21_21") (pintype "bidirectional"))
    )
    (net (code "38") (name "PREVGL") (class "Default")
      (node (ref "D4") (pin "2") (pinfunction "A_2") (pintype "bidirectional"))
      (node (ref "EPD_C11") (pin "1") (pinfunction "1_1") (pintype "passive"))
      (node (ref "J1") (pin "23") (pinfunction "23_23") (pintype "bidirectional"))
    )
    (net (code "39") (name "RESE") (class "Default")
      (node (ref "J1") (pin "3") (pinfunction "3_3") (pintype "bidirectional"))
      (node (ref "Q3") (pin "2") (pinfunction "S_2") (pintype "bidirectional"))
      (node (ref "R3") (pin "1") (pinfunction "1_1") (pintype "passive"))
    )
    (net (code "40") (name "RESE'") (class "Default")
      (node (ref "R2") (pin "2") (pinfunction "2_2") (pintype "passive"))
      (node (ref "R3") (pin "2") (pinfunction "2_2") (pintype "passive"))
      (node (ref "SJ1") (pin "2") (pinfunction "2_2") (pintype "passive"))
    )
    (net (code "41") (name "RESET") (class "Default")
      (node (ref "C5") (pin "1") (pinfunction "1_1") (pintype "passive"))
      (node (ref "IC1") (pin "1") (pinfunction "VOUT_1") (pintype "bidirectional"))
      (node (ref "RESET_BUTTON") (pin "3") (pinfunction "3_3") (pintype "passive"))
      (node (ref "RESET_BUTTON") (pin "4") (pinfunction "4_4") (pintype "passive"))
      (node (ref "R_RESET") (pin "1") (pinfunction "1_1") (pintype "passive"))
      (node (ref "U2") (pin "3") (pinfunction "EN_3") (pintype "input"))
    )
    (net (code "42") (name "RTC_RST") (class "Default")
      (node (ref "U2") (pin "16") (pinfunction "IO18_16") (pintype "bidirectional"))
      (node (ref "U3") (pin "4") (pinfunction "~{RST}_4") (pintype "input"))
    )
    (net (code "43") (name "RX") (class "Default")
      (node (ref "RX") (pin "TP") (pinfunction "TP_TP") (pintype "input"))
      (node (ref "U2") (pin "24") (pinfunction "RXD0/GPIO17_24") (pintype "bidirectional"))
    )
    (net (code "44") (name "SCK") (class "Default")
      (node (ref "D10") (pin "2") (pinfunction "2_2") (pintype "passive"))
      (node (ref "J1") (pin "13") (pinfunction "13_13") (pintype "bidirectional"))
      (node (ref "J4") (pin "P5") (pinfunction "CLK_P5") (pintype "bidirectional"))
      (node (ref "R6") (pin "1") (pinfunction "1_1") (pintype "passive"))
      (node (ref "SCK") (pin "TP") (pinfunction "TP_TP") (pintype "input"))
      (node (ref "U1") (pin "6") (pinfunction "CLK_6") (pintype "input"))
      (node (ref "U2") (pin "6") (pinfunction "IO6_6") (pintype "bidirectional"))
    )
    (net (code "45") (name "SCL") (class "Default")
      (node (ref "J3") (pin "4") (pinfunction "4_4") (pintype "passive"))
      (node (ref "R2-PINH") (pin "1") (pinfunction "1_1") (pintype "passive"))
      (node (ref "SENSOR2") (pin "4") (pinfunction "SCK_4") (pintype "input"))
      (node (ref "U2") (pin "20") (pinfunction "IO22_20") (pintype "bidirectional"))
      (node (ref "U3") (pin "16") (pinfunction "SCL_16") (pintype "input"))
      (node (ref "U4") (pin "7") (pinfunction "SCL_7") (pintype "input"))
    )
    (net (code "46") (name "SDA") (class "Default")
      (node (ref "J3") (pin "3") (pinfunction "3_3") (pintype "passive"))
      (node (ref "R1-PINH") (pin "1") (pinfunction "1_1") (pintype "passive"))
      (node (ref "SENSOR2") (pin "3") (pinfunction "SDI_3") (pintype "bidirectional"))
      (node (ref "U2") (pin "19") (pinfunction "IO21_19") (pintype "bidirectional"))
      (node (ref "U3") (pin "15") (pinfunction "SDA_15") (pintype "bidirectional"))
      (node (ref "U4") (pin "8") (pinfunction "SDA_8") (pintype "bidirectional"))
    )
    (net (code "47") (name "SRC") (class "Default")
      (node (ref "C4") (pin "2") (pinfunction "2_2") (pintype "passive"))
      (node (ref "D5") (pin "2") (pinfunction "A_2") (pintype "bidirectional"))
      (node (ref "L1") (pin "1") (pinfunction "1_1") (pintype "passive"))
      (node (ref "Q3") (pin "3") (pinfunction "D_3") (pintype "bidirectional"))
    )
    (net (code "48") (name "SS_SD") (class "Default")
      (node (ref "D8") (pin "2") (pinfunction "2_2") (pintype "passive"))
      (node (ref "J4") (pin "P2") (pinfunction "CD/DAT3_P2") (pintype "bidirectional"))
      (node (ref "R10") (pin "1") (pinfunction "1_1") (pintype "passive"))
      (node (ref "U2") (pin "4") (pinfunction "IO4_4") (pintype "bidirectional"))
    )
    (net (code "49") (name "TX") (class "Default")
      (node (ref "TX") (pin "TP") (pinfunction "TP_TP") (pintype "input"))
      (node (ref "U2") (pin "25") (pinfunction "TXD0/GPIO16_25") (pintype "bidirectional"))
    )
    (net (code "50") (name "USB_D+") (class "Default")
      (node (ref "D1") (pin "1") (pinfunction "I/O1_1_1") (pintype "bidirectional"))
      (node (ref "U2") (pin "14") (pinfunction "IO13_14") (pintype "bidirectional"))
    )
    (net (code "51") (name "USB_D-") (class "Default")
      (node (ref "D1") (pin "3") (pinfunction "I/O2_1_3") (pintype "bidirectional"))
      (node (ref "U2") (pin "13") (pinfunction "IO12_13") (pintype "bidirectional"))
    )
    (net (code "52") (name "VBAT") (class "Default")
      (node (ref "C2_BAT") (pin "1") (pinfunction "1_1") (pintype "passive"))
      (node (ref "MCP73831") (pin "3") (pinfunction "VBAT_3") (pintype "power_in"))
      (node (ref "Q1") (pin "3") (pinfunction "D_3") (pintype "bidirectional"))
      (node (ref "U4") (pin "2") (pinfunction "CELL_2") (pintype "power_in"))
      (node (ref "U4") (pin "3") (pinfunction "VDD_3") (pintype "power_in"))
      (node (ref "VBAT") (pin "TP") (pinfunction "TP_TP") (pintype "input"))
    )
    (net (code "53") (name "VBUS") (class "Default")
      (node (ref "C1_BAT") (pin "1") (pinfunction "1_1") (pintype "passive"))
      (node (ref "C4_USB") (pin "1") (pinfunction "1_1") (pintype "passive"))
      (node (ref "C5_USB") (pin "1") (pinfunction "1_1") (pintype "passive"))
      (node (ref "CHG_LED") (pin "A") (pinfunction "A_A") (pintype "passive"))
      (node (ref "D1") (pin "5") (pinfunction "VBUS_5") (pintype "bidirectional"))
      (node (ref "D2") (pin "2") (pinfunction "ANODE_2") (pintype "bidirectional"))
      (node (ref "MCP73831") (pin "4") (pinfunction "VIN_4") (pintype "power_in"))
      (node (ref "PFMF.050.1") (pin "2") (pinfunction "2_2") (pintype "passive"))
      (node (ref "Q1") (pin "1") (pinfunction "G_1") (pintype "bidirectional"))
      (node (ref "R1_PWRUSB") (pin "2") (pinfunction "2_2") (pintype "passive"))
      (node (ref "VBUS") (pin "TP") (pinfunction "TP_TP") (pintype "input"))
    )
    (net (code "54") (name "VRTC") (class "Default")
      (node (ref "C10_SUPERCAP") (pin "2") (pinfunction "2_2") (pintype "passive"))
      (node (ref "C8") (pin "1") (pinfunction "1_1") (pintype "passive"))
      (node (ref "R_CAPACITATOR") (pin "1") (pinfunction "1_1") (pintype "passive"))
      (node (ref "U3") (pin "14") (pinfunction "VBAT_14") (pintype "power_in"))
    )
    (net (code "55") (name "VUSB") (class "Default")
      (node (ref "J2") (pin "A4") (pinfunction "A4_A4") (pintype "bidirectional"))
      (node (ref "J2") (pin "A9") (pinfunction "A9_A9") (pintype "bidirectional"))
      (node (ref "J2") (pin "B4") (pinfunction "B4_B4") (pintype "bidirectional"))
      (node (ref "J2") (pin "B9") (pinfunction "B9_B9") (pintype "bidirectional"))
      (node (ref "PFMF.050.1") (pin "1") (pinfunction "1_1") (pintype "passive"))
    )
    (net (code "56") (name "unconnected-(IC1-NC-Pad4)") (class "Default")
      (node (ref "IC1") (pin "4") (pinfunction "NC_4") (pintype "no_connect"))
    )
    (net (code "57") (name "unconnected-(IC4-NC-Pad4)") (class "Default")
      (node (ref "IC4") (pin "4") (pinfunction "NC_4") (pintype "no_connect"))
    )
    (net (code "58") (name "unconnected-(J1-Pad1)") (class "Default")
      (node (ref "J1") (pin "1") (pinfunction "1_1") (pintype "bidirectional"))
    )
    (net (code "59") (name "unconnected-(J1-Pad6)") (class "Default")
      (node (ref "J1") (pin "6") (pinfunction "6_6") (pintype "bidirectional"))
    )
    (net (code "60") (name "unconnected-(J1-Pad7)") (class "Default")
      (node (ref "J1") (pin "7") (pinfunction "7_7") (pintype "bidirectional"))
    )
    (net (code "61") (name "unconnected-(J2-PadA8)") (class "Default")
      (node (ref "J2") (pin "A8") (pinfunction "A8_A8") (pintype "bidirectional"))
    )
    (net (code "62") (name "unconnected-(J2-PadB8)") (class "Default")
      (node (ref "J2") (pin "B8") (pinfunction "B8_B8") (pintype "bidirectional"))
    )
    (net (code "63") (name "unconnected-(J4-DAT1-PadP8)") (class "Default")
      (node (ref "J4") (pin "P8") (pinfunction "DAT1_P8") (pintype "bidirectional"))
    )
    (net (code "64") (name "unconnected-(J4-DAT2-PadP1)") (class "Default")
      (node (ref "J4") (pin "P1") (pinfunction "DAT2_P1") (pintype "bidirectional"))
    )
    (net (code "65") (name "unconnected-(J4-DETECTION_1-PadS1)") (class "Default")
      (node (ref "J4") (pin "S1") (pinfunction "DETECTION_1_S1") (pintype "bidirectional"))
    )
    (net (code "66") (name "unconnected-(J4-DETECTION_2-PadS2)") (class "Default")
      (node (ref "J4") (pin "S2") (pinfunction "DETECTION_2_S2") (pintype "bidirectional"))
    )
    (net (code "67") (name "unconnected-(U2-NC-Pad22)") (class "Default")
      (node (ref "U2") (pin "22") (pinfunction "NC_22") (pintype "no_connect"))
    )
    (net (code "68") (name "unconnected-(U4-~{ALERT}-Pad5)") (class "Default")
      (node (ref "U4") (pin "5") (pinfunction "~{ALERT}_5") (pintype "output"))
    )
  )
)
